# NEO-Pi-RAK-3.net
KiCad netlist of a schematic drawn in EAGLE
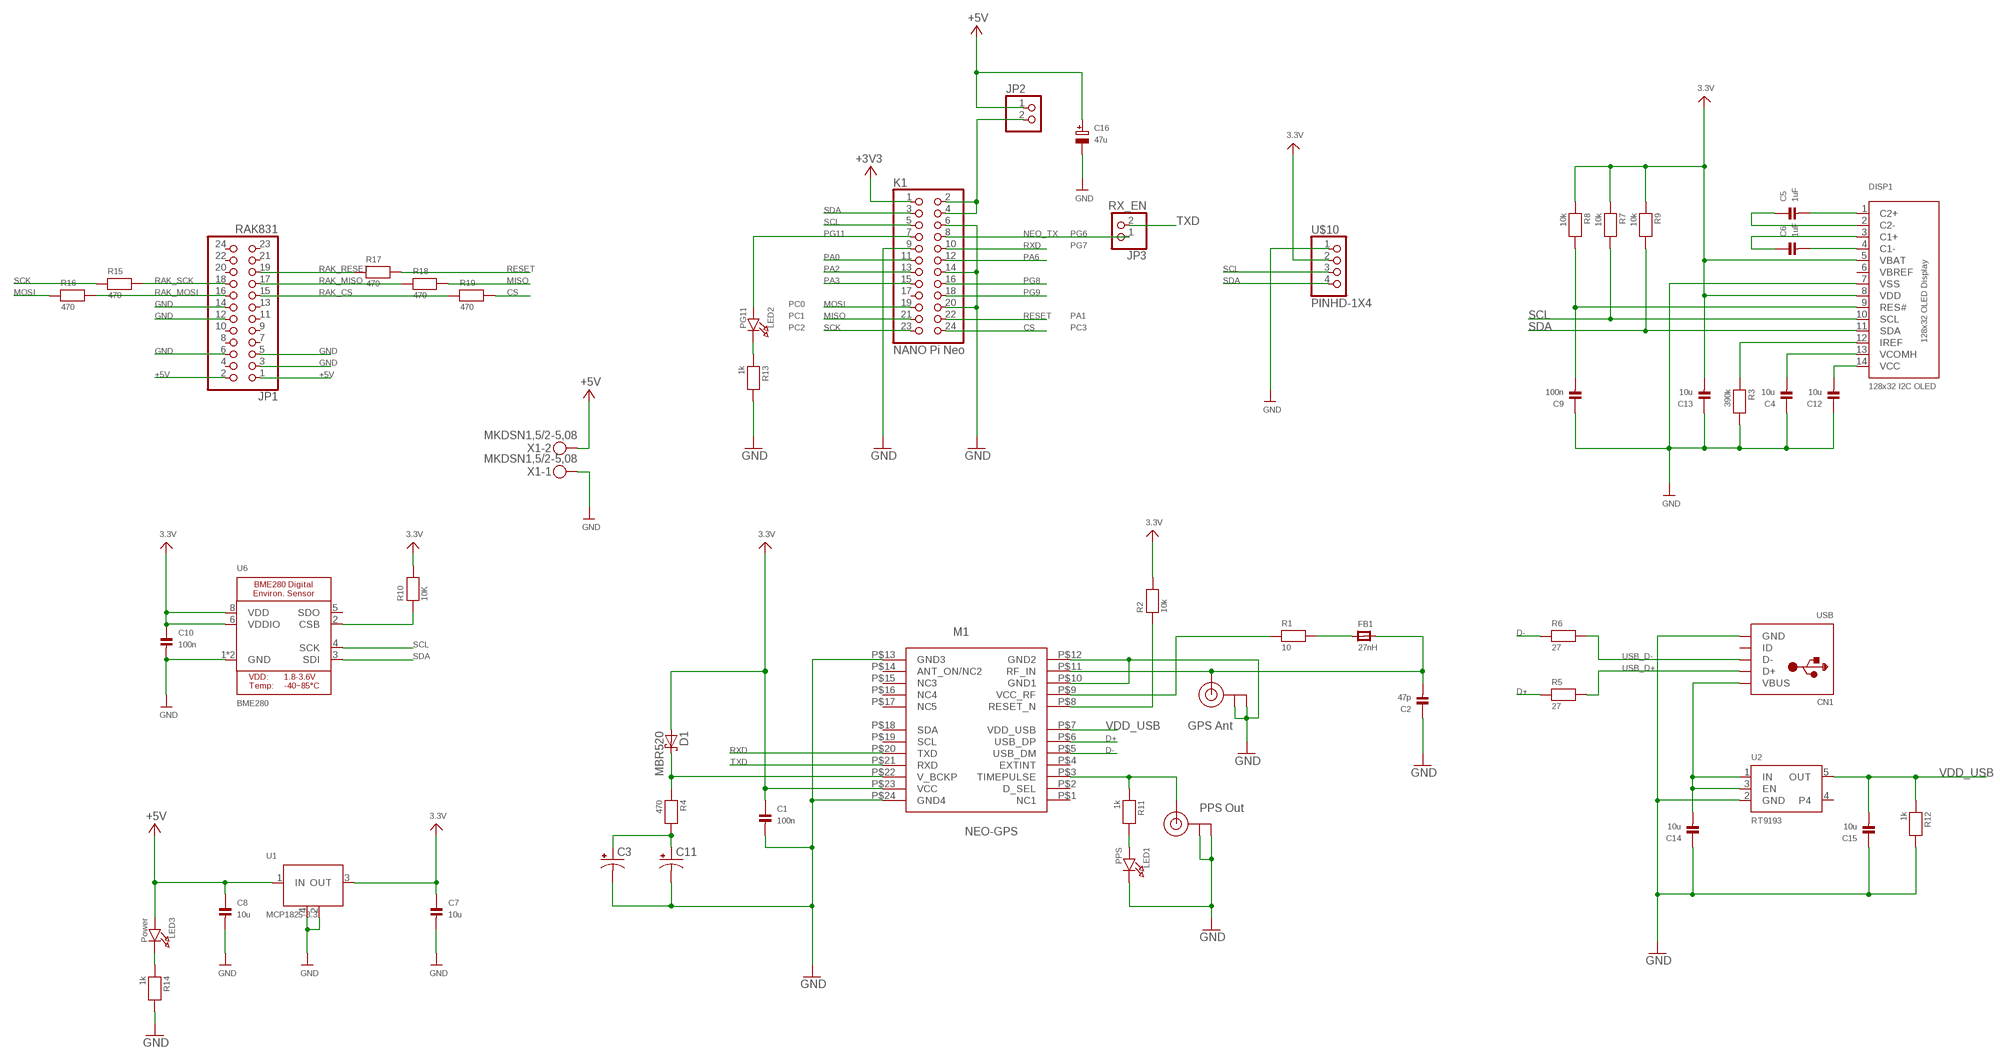
[diagram p0: schematic, sheet 1]

(export (version "E")
  (design (tool "Eeschema 10.0.6"))
  (components
    (comp (ref "C1")
      (value "100n")
      (footprint "eagle-import:0805")
      (libsource (lib "eagle-import") (part "CAP_CERAMIC0805"))
    )
    (comp (ref "C2")
      (value "47p")
      (footprint "eagle-import:0805")
      (libsource (lib "eagle-import") (part "CAP_CERAMIC0805"))
    )
    (comp (ref "C3")
      (value "SUPERCAP")
      (footprint "eagle-import:414-VA5R")
      (libsource (lib "eagle-import") (part "adafruit_SUPERCAP"))
    )
    (comp (ref "C4")
      (value "10u")
      (footprint "eagle-import:0805")
      (libsource (lib "eagle-import") (part "CAP_CERAMIC0805"))
    )
    (comp (ref "C5")
      (value "1uF")
      (footprint "eagle-import:0805")
      (libsource (lib "eagle-import") (part "CAP_CERAMIC0805"))
    )
    (comp (ref "C6")
      (value "1uF")
      (footprint "eagle-import:0805")
      (libsource (lib "eagle-import") (part "CAP_CERAMIC0805"))
    )
    (comp (ref "C7")
      (value "10u")
      (footprint "eagle-import:0805")
      (libsource (lib "eagle-import") (part "CAP_CERAMIC0805"))
    )
    (comp (ref "C8")
      (value "10u")
      (footprint "eagle-import:0805")
      (libsource (lib "eagle-import") (part "CAP_CERAMIC0805"))
    )
    (comp (ref "C9")
      (value "100n")
      (footprint "eagle-import:0805")
      (libsource (lib "eagle-import") (part "CAP_CERAMIC0805"))
    )
    (comp (ref "C10")
      (value "100n")
      (footprint "eagle-import:0805")
      (libsource (lib "eagle-import") (part "CAP_CERAMIC0805"))
    )
    (comp (ref "C11")
      (value "SUPERCAP")
      (footprint "eagle-import:SUPERCAP")
      (libsource (lib "eagle-import") (part "SUPERCAP"))
    )
    (comp (ref "C12")
      (value "10u")
      (footprint "eagle-import:0805")
      (libsource (lib "eagle-import") (part "CAP_CERAMIC0805"))
    )
    (comp (ref "C13")
      (value "10u")
      (footprint "eagle-import:0805")
      (libsource (lib "eagle-import") (part "CAP_CERAMIC0805"))
    )
    (comp (ref "C14")
      (value "10u")
      (footprint "eagle-import:0805")
      (libsource (lib "eagle-import") (part "CAP_CERAMIC0805"))
    )
    (comp (ref "C15")
      (value "10u")
      (footprint "eagle-import:0805")
      (libsource (lib "eagle-import") (part "CAP_CERAMIC0805"))
    )
    (comp (ref "C16")
      (value "47u")
      (footprint "eagle-import:EIA3528-21_B-R")
      (libsource (lib "eagle-import") (part "CAP_TANTALUMB/3528_REFLOW"))
    )
    (comp (ref "CN1")
      (value "USB")
      (footprint "eagle-import:USB-MINIB")
      (libsource (lib "eagle-import") (part "USBMINIB"))
    )
    (comp (ref "D1")
      (value "MBR520")
      (footprint "eagle-import:SOD123")
      (libsource (lib "eagle-import") (part "MBR0520"))
    )
    (comp (ref "DISP1")
      (value "128x32 I2C OLED")
      (footprint "eagle-import:0.91-128X32-OLED-I2C")
      (libsource (lib "eagle-import") (part "0.91-128X32-OLED-I2C"))
    )
    (comp (ref "FB1")
      (value "27nH")
      (footprint "eagle-import:0805")
      (libsource (lib "eagle-import") (part "FERRITE0805"))
    )
    (comp (ref "JP1")
      (value "RAK831")
      (footprint "eagle-import:2X12")
      (libsource (lib "eagle-import") (part "PINHD-2X12"))
    )
    (comp (ref "JP2")
      (value "PINHD-1X2")
      (footprint "eagle-import:1X02")
      (libsource (lib "eagle-import") (part "PINHD-1X2"))
    )
    (comp (ref "JP3")
      (value "RX_EN")
      (footprint "eagle-import:1X02")
      (libsource (lib "eagle-import") (part "PINHD-1X2"))
    )
    (comp (ref "K1")
      (value "NANO Pi Neo")
      (footprint "eagle-import:2X12")
      (libsource (lib "eagle-import") (part "PINHD-2X12"))
    )
    (comp (ref "LED1")
      (value "PPS")
      (footprint "eagle-import:CHIPLED_0805")
      (libsource (lib "eagle-import") (part "LED0805"))
    )
    (comp (ref "LED2")
      (value "PG11")
      (footprint "eagle-import:CHIPLED_0805")
      (libsource (lib "eagle-import") (part "LED0805"))
    )
    (comp (ref "LED3")
      (value "Power")
      (footprint "eagle-import:CHIPLED_0805")
      (libsource (lib "eagle-import") (part "LED0805"))
    )
    (comp (ref "M1")
      (value "NEO-GPS")
      (footprint "eagle-import:NEO_GPS")
      (libsource (lib "eagle-import") (part "NEO-GPS"))
    )
    (comp (ref "R1")
      (value "10")
      (footprint "eagle-import:0805")
      (libsource (lib "eagle-import") (part "RESISTOR0805"))
    )
    (comp (ref "R2")
      (value "10k")
      (footprint "eagle-import:0805")
      (libsource (lib "eagle-import") (part "RESISTOR0805"))
    )
    (comp (ref "R3")
      (value "390k")
      (footprint "eagle-import:0805")
      (libsource (lib "eagle-import") (part "RESISTOR0805"))
    )
    (comp (ref "R4")
      (value "470")
      (footprint "eagle-import:0805")
      (libsource (lib "eagle-import") (part "RESISTOR0805"))
    )
    (comp (ref "R5")
      (value "27")
      (footprint "eagle-import:0805")
      (libsource (lib "eagle-import") (part "RESISTOR0805"))
    )
    (comp (ref "R6")
      (value "27")
      (footprint "eagle-import:0805")
      (libsource (lib "eagle-import") (part "RESISTOR0805"))
    )
    (comp (ref "R7")
      (value "10k")
      (footprint "eagle-import:0805")
      (libsource (lib "eagle-import") (part "RESISTOR0805"))
    )
    (comp (ref "R8")
      (value "10k")
      (footprint "eagle-import:0805")
      (libsource (lib "eagle-import") (part "RESISTOR0805"))
    )
    (comp (ref "R9")
      (value "10k")
      (footprint "eagle-import:0805")
      (libsource (lib "eagle-import") (part "RESISTOR0805"))
    )
    (comp (ref "R10")
      (value "10K")
      (footprint "eagle-import:0805")
      (libsource (lib "eagle-import") (part "RESISTOR0805"))
    )
    (comp (ref "R11")
      (value "1k")
      (footprint "eagle-import:0805")
      (libsource (lib "eagle-import") (part "RESISTOR0805"))
    )
    (comp (ref "R12")
      (value "1k")
      (footprint "eagle-import:0805")
      (libsource (lib "eagle-import") (part "RESISTOR0805"))
    )
    (comp (ref "R13")
      (value "1k")
      (footprint "eagle-import:0805")
      (libsource (lib "eagle-import") (part "RESISTOR0805"))
    )
    (comp (ref "R14")
      (value "1k")
      (footprint "eagle-import:0805")
      (libsource (lib "eagle-import") (part "RESISTOR0805"))
    )
    (comp (ref "R15")
      (value "470")
      (footprint "eagle-import:0805")
      (libsource (lib "eagle-import") (part "RESISTOR0805"))
    )
    (comp (ref "R16")
      (value "470")
      (footprint "eagle-import:0805")
      (libsource (lib "eagle-import") (part "RESISTOR0805"))
    )
    (comp (ref "R17")
      (value "470")
      (footprint "eagle-import:0805")
      (libsource (lib "eagle-import") (part "RESISTOR0805"))
    )
    (comp (ref "R18")
      (value "470")
      (footprint "eagle-import:0805")
      (libsource (lib "eagle-import") (part "RESISTOR0805"))
    )
    (comp (ref "R19")
      (value "470")
      (footprint "eagle-import:0805")
      (libsource (lib "eagle-import") (part "RESISTOR0805"))
    )
    (comp (ref "U$1")
      (value "U.FL")
      (footprint "eagle-import:U.FL")
      (libsource (lib "eagle-import") (part "U.FL"))
    )
    (comp (ref "U$2")
      (value "U.FL")
      (footprint "eagle-import:U.FL")
      (libsource (lib "eagle-import") (part "U.FL"))
    )
    (comp (ref "U$10")
      (value "PINHD-1X4")
      (footprint "eagle-import:1X04-BIG")
      (libsource (lib "eagle-import") (part "PINHD-1X4"))
    )
    (comp (ref "U1")
      (value "MCP1825-3.3")
      (footprint "eagle-import:UA78M05")
      (libsource (lib "eagle-import") (part "MCP1825ST-3.3"))
    )
    (comp (ref "U2")
      (value "RT9193")
      (footprint "eagle-import:SOT23-5")
      (libsource (lib "eagle-import") (part "VREG_SOT23-5"))
    )
    (comp (ref "U6")
      (value "BME280")
      (footprint "eagle-import:BME280")
      (libsource (lib "eagle-import") (part "BME280"))
    )
    (comp (ref "X1")
      (value "MKDSN1,5/2-5,08")
      (footprint "eagle-import:MKDSN1,5_2-5,08")
      (libsource (lib "eagle-import") (part "MKDSN1,5/2-5,08"))
    )
  )
  (nets
    (net (code "1") (name "+3V3") (class "Default")
      (node (ref "K1") (pin "1") (pinfunction "1_1") (pintype "passive"))
    )
    (net (code "2") (name "+5V") (class "Default")
      (node (ref "C16") (pin "+") (pinfunction "+_+") (pintype "passive"))
      (node (ref "C8") (pin "1") (pinfunction "P$1_1") (pintype "passive"))
      (node (ref "JP1") (pin "1") (pinfunction "1_1") (pintype "passive"))
      (node (ref "JP1") (pin "2") (pinfunction "2_2") (pintype "passive"))
      (node (ref "JP2") (pin "1") (pinfunction "1_1") (pintype "passive"))
      (node (ref "LED3") (pin "A") (pinfunction "A_A") (pintype "passive"))
      (node (ref "U1") (pin "1") (pinfunction "IN_1") (pintype "input"))
      (node (ref "X1") (pin "2") (pinfunction "KL_2") (pintype "passive"))
    )
    (net (code "3") (name "/CS") (class "Default")
      (node (ref "K1") (pin "24") (pinfunction "24_24") (pintype "passive"))
      (node (ref "R19") (pin "2") (pinfunction "2_2") (pintype "passive"))
    )
    (net (code "4") (name "/D+") (class "Default")
      (node (ref "M1") (pin "P$6") (pinfunction "USB_DP_P$6") (pintype "bidirectional"))
      (node (ref "R5") (pin "1") (pinfunction "1_1") (pintype "passive"))
    )
    (net (code "5") (name "/D-") (class "Default")
      (node (ref "M1") (pin "P$5") (pinfunction "USB_DM_P$5") (pintype "bidirectional"))
      (node (ref "R6") (pin "1") (pinfunction "1_1") (pintype "passive"))
    )
    (net (code "6") (name "/MISO") (class "Default")
      (node (ref "K1") (pin "21") (pinfunction "21_21") (pintype "passive"))
      (node (ref "R18") (pin "2") (pinfunction "2_2") (pintype "passive"))
    )
    (net (code "7") (name "/MOSI") (class "Default")
      (node (ref "K1") (pin "19") (pinfunction "19_19") (pintype "passive"))
      (node (ref "R16") (pin "1") (pinfunction "1_1") (pintype "passive"))
    )
    (net (code "8") (name "/NEO_TX") (class "Default")
      (node (ref "JP3") (pin "1") (pinfunction "1_1") (pintype "passive"))
      (node (ref "K1") (pin "8") (pinfunction "8_8") (pintype "passive"))
    )
    (net (code "9") (name "/PA0") (class "Default")
      (node (ref "K1") (pin "11") (pinfunction "11_11") (pintype "passive"))
    )
    (net (code "10") (name "/PA2") (class "Default")
      (node (ref "K1") (pin "13") (pinfunction "13_13") (pintype "passive"))
    )
    (net (code "11") (name "/PA3") (class "Default")
      (node (ref "K1") (pin "15") (pinfunction "15_15") (pintype "passive"))
    )
    (net (code "12") (name "/PA6") (class "Default")
      (node (ref "K1") (pin "12") (pinfunction "12_12") (pintype "passive"))
    )
    (net (code "13") (name "/PG8") (class "Default")
      (node (ref "K1") (pin "16") (pinfunction "16_16") (pintype "passive"))
    )
    (net (code "14") (name "/PG9") (class "Default")
      (node (ref "K1") (pin "18") (pinfunction "18_18") (pintype "passive"))
    )
    (net (code "15") (name "/PG11") (class "Default")
      (node (ref "K1") (pin "7") (pinfunction "7_7") (pintype "passive"))
      (node (ref "LED2") (pin "A") (pinfunction "A_A") (pintype "passive"))
    )
    (net (code "16") (name "/RAK_CS") (class "Default")
      (node (ref "JP1") (pin "15") (pinfunction "15_15") (pintype "passive"))
      (node (ref "R19") (pin "1") (pinfunction "1_1") (pintype "passive"))
    )
    (net (code "17") (name "/RAK_MISO") (class "Default")
      (node (ref "JP1") (pin "17") (pinfunction "17_17") (pintype "passive"))
      (node (ref "R18") (pin "1") (pinfunction "1_1") (pintype "passive"))
    )
    (net (code "18") (name "/RAK_MOSI") (class "Default")
      (node (ref "JP1") (pin "16") (pinfunction "16_16") (pintype "passive"))
      (node (ref "R16") (pin "2") (pinfunction "2_2") (pintype "passive"))
    )
    (net (code "19") (name "/RAK_RESET") (class "Default")
      (node (ref "JP1") (pin "19") (pinfunction "19_19") (pintype "passive"))
      (node (ref "R17") (pin "1") (pinfunction "1_1") (pintype "passive"))
    )
    (net (code "20") (name "/RAK_SCK") (class "Default")
      (node (ref "JP1") (pin "18") (pinfunction "18_18") (pintype "passive"))
      (node (ref "R15") (pin "2") (pinfunction "2_2") (pintype "passive"))
    )
    (net (code "21") (name "/RESET") (class "Default")
      (node (ref "K1") (pin "22") (pinfunction "22_22") (pintype "passive"))
      (node (ref "R17") (pin "2") (pinfunction "2_2") (pintype "passive"))
    )
    (net (code "22") (name "/RXD") (class "Default")
      (node (ref "K1") (pin "10") (pinfunction "10_10") (pintype "passive"))
      (node (ref "M1") (pin "P$20") (pinfunction "TXD_P$20") (pintype "output"))
    )
    (net (code "23") (name "/SCK") (class "Default")
      (node (ref "K1") (pin "23") (pinfunction "23_23") (pintype "passive"))
      (node (ref "R15") (pin "1") (pinfunction "1_1") (pintype "passive"))
    )
    (net (code "24") (name "/SCL") (class "Default")
      (node (ref "DISP1") (pin "10") (pinfunction "SCL_10") (pintype "bidirectional"))
      (node (ref "K1") (pin "5") (pinfunction "5_5") (pintype "passive"))
      (node (ref "R7") (pin "2") (pinfunction "2_2") (pintype "passive"))
      (node (ref "U$10") (pin "3") (pinfunction "3_3") (pintype "passive"))
      (node (ref "U6") (pin "4") (pinfunction "SCK_4") (pintype "input"))
    )
    (net (code "25") (name "/SDA") (class "Default")
      (node (ref "DISP1") (pin "11") (pinfunction "SDA_11") (pintype "bidirectional"))
      (node (ref "K1") (pin "3") (pinfunction "3_3") (pintype "passive"))
      (node (ref "R9") (pin "2") (pinfunction "2_2") (pintype "passive"))
      (node (ref "U$10") (pin "4") (pinfunction "4_4") (pintype "passive"))
      (node (ref "U6") (pin "3") (pinfunction "SDI_3") (pintype "input"))
    )
    (net (code "26") (name "/TXD") (class "Default")
      (node (ref "JP3") (pin "2") (pinfunction "2_2") (pintype "passive"))
      (node (ref "M1") (pin "P$21") (pinfunction "RXD_P$21") (pintype "input"))
    )
    (net (code "27") (name "/USB_D+") (class "Default")
      (node (ref "CN1") (pin "D+") (pinfunction "D+_D+") (pintype "bidirectional"))
      (node (ref "R5") (pin "2") (pinfunction "2_2") (pintype "passive"))
    )
    (net (code "28") (name "/USB_D-") (class "Default")
      (node (ref "CN1") (pin "D-") (pinfunction "D-_D-") (pintype "bidirectional"))
      (node (ref "R6") (pin "2") (pinfunction "2_2") (pintype "passive"))
    )
    (net (code "29") (name "/VBREF") (class "Default")
      (node (ref "DISP1") (pin "6") (pinfunction "VBREF_6") (pintype "power_in"))
    )
    (net (code "30") (name "/VDD_USB") (class "Default")
      (node (ref "C15") (pin "2") (pinfunction "P$2_2") (pintype "passive"))
      (node (ref "M1") (pin "P$7") (pinfunction "VDD_USB_P$7") (pintype "input"))
      (node (ref "R12") (pin "1") (pinfunction "1_1") (pintype "passive"))
      (node (ref "U2") (pin "5") (pinfunction "OUT_5") (pintype "bidirectional"))
    )
    (net (code "31") (name "3.3V") (class "Default")
      (node (ref "C1") (pin "1") (pinfunction "P$1_1") (pintype "passive"))
      (node (ref "C10") (pin "1") (pinfunction "P$1_1") (pintype "passive"))
      (node (ref "C13") (pin "2") (pinfunction "P$2_2") (pintype "passive"))
      (node (ref "C7") (pin "1") (pinfunction "P$1_1") (pintype "passive"))
      (node (ref "D1") (pin "A") (pinfunction "A_A") (pintype "passive"))
      (node (ref "DISP1") (pin "5") (pinfunction "VBAT_5") (pintype "power_in"))
      (node (ref "DISP1") (pin "8") (pinfunction "VDD_8") (pintype "power_in"))
      (node (ref "M1") (pin "P$23") (pinfunction "VCC_P$23") (pintype "input"))
      (node (ref "R10") (pin "2") (pinfunction "2_2") (pintype "passive"))
      (node (ref "R2") (pin "2") (pinfunction "2_2") (pintype "passive"))
      (node (ref "R7") (pin "1") (pinfunction "1_1") (pintype "passive"))
      (node (ref "R8") (pin "1") (pinfunction "1_1") (pintype "passive"))
      (node (ref "R9") (pin "1") (pinfunction "1_1") (pintype "passive"))
      (node (ref "U$10") (pin "2") (pinfunction "2_2") (pintype "passive"))
      (node (ref "U1") (pin "3") (pinfunction "OUT_3") (pintype "passive"))
      (node (ref "U6") (pin "6") (pinfunction "VDDIO_6") (pintype "power_in"))
      (node (ref "U6") (pin "8") (pinfunction "VDD_8") (pintype "power_in"))
    )
    (net (code "32") (name "GND") (class "Default")
      (node (ref "C1") (pin "2") (pinfunction "P$2_2") (pintype "passive"))
      (node (ref "C10") (pin "2") (pinfunction "P$2_2") (pintype "passive"))
      (node (ref "C11") (pin "P$2") (pinfunction "-_P$2") (pintype "passive"))
      (node (ref "C12") (pin "1") (pinfunction "P$1_1") (pintype "passive"))
      (node (ref "C13") (pin "1") (pinfunction "P$1_1") (pintype "passive"))
      (node (ref "C14") (pin "1") (pinfunction "P$1_1") (pintype "passive"))
      (node (ref "C15") (pin "1") (pinfunction "P$1_1") (pintype "passive"))
      (node (ref "C16") (pin "-") (pinfunction "-_-") (pintype "passive"))
      (node (ref "C2") (pin "1") (pinfunction "P$1_1") (pintype "passive"))
      (node (ref "C3") (pin "-") (pinfunction "-_-") (pintype "passive"))
      (node (ref "C4") (pin "1") (pinfunction "P$1_1") (pintype "passive"))
      (node (ref "C7") (pin "2") (pinfunction "P$2_2") (pintype "passive"))
      (node (ref "C8") (pin "2") (pinfunction "P$2_2") (pintype "passive"))
      (node (ref "C9") (pin "1") (pinfunction "P$1_1") (pintype "passive"))
      (node (ref "CN1") (pin "GND") (pinfunction "GND_GND") (pintype "power_in"))
      (node (ref "DISP1") (pin "7") (pinfunction "VSS_7") (pintype "power_in"))
      (node (ref "JP1") (pin "12") (pinfunction "12_12") (pintype "passive"))
      (node (ref "JP1") (pin "14") (pinfunction "14_14") (pintype "passive"))
      (node (ref "JP1") (pin "3") (pinfunction "3_3") (pintype "passive"))
      (node (ref "JP1") (pin "5") (pinfunction "5_5") (pintype "passive"))
      (node (ref "JP1") (pin "6") (pinfunction "6_6") (pintype "passive"))
      (node (ref "K1") (pin "14") (pinfunction "14_14") (pintype "passive"))
      (node (ref "K1") (pin "20") (pinfunction "20_20") (pintype "passive"))
      (node (ref "K1") (pin "6") (pinfunction "6_6") (pintype "passive"))
      (node (ref "K1") (pin "9") (pinfunction "9_9") (pintype "passive"))
      (node (ref "LED1") (pin "C") (pinfunction "C_C") (pintype "passive"))
      (node (ref "M1") (pin "P$10") (pinfunction "GND1_P$10") (pintype "input"))
      (node (ref "M1") (pin "P$12") (pinfunction "GND2_P$12") (pintype "input"))
      (node (ref "M1") (pin "P$13") (pinfunction "GND3_P$13") (pintype "input"))
      (node (ref "M1") (pin "P$24") (pinfunction "GND4_P$24") (pintype "input"))
      (node (ref "R12") (pin "2") (pinfunction "2_2") (pintype "passive"))
      (node (ref "R13") (pin "2") (pinfunction "2_2") (pintype "passive"))
      (node (ref "R14") (pin "2") (pinfunction "2_2") (pintype "passive"))
      (node (ref "R3") (pin "2") (pinfunction "2_2") (pintype "passive"))
      (node (ref "U$1") (pin "P$1") (pinfunction "GND_P$1") (pintype "bidirectional"))
      (node (ref "U$1") (pin "P$2") (pinfunction "GND_P$2") (pintype "bidirectional"))
      (node (ref "U$10") (pin "1") (pinfunction "1_1") (pintype "passive"))
      (node (ref "U$2") (pin "P$1") (pinfunction "GND_P$1") (pintype "bidirectional"))
      (node (ref "U$2") (pin "P$2") (pinfunction "GND_P$2") (pintype "bidirectional"))
      (node (ref "U1") (pin "2") (pinfunction "COMMON1_2") (pintype "passive"))
      (node (ref "U1") (pin "4") (pinfunction "COMMON2_4") (pintype "passive"))
      (node (ref "U2") (pin "2") (pinfunction "GND_2") (pintype "bidirectional"))
      (node (ref "U6") (pin "1") (pinfunction "GND_1") (pintype "power_in"))
      (node (ref "U6") (pin "7") (pinfunction "GND_7") (pintype "power_in"))
      (node (ref "X1") (pin "1") (pinfunction "KL_1") (pintype "passive"))
    )
    (net (code "33") (name "Net-(C2-P$2)") (class "Default")
      (node (ref "C2") (pin "2") (pinfunction "P$2_2") (pintype "passive"))
      (node (ref "FB1") (pin "2") (pinfunction "P$2_2") (pintype "passive"))
      (node (ref "M1") (pin "P$11") (pinfunction "RF_IN_P$11") (pintype "input"))
      (node (ref "U$1") (pin "P$3") (pinfunction "SIGNAL_P$3") (pintype "bidirectional"))
    )
    (net (code "34") (name "Net-(C4-P$2)") (class "Default")
      (node (ref "C4") (pin "2") (pinfunction "P$2_2") (pintype "passive"))
      (node (ref "DISP1") (pin "13") (pinfunction "VCOMH_13") (pintype "power_in"))
    )
    (net (code "35") (name "Net-(C5-P$1)") (class "Default")
      (node (ref "C5") (pin "1") (pinfunction "P$1_1") (pintype "passive"))
      (node (ref "DISP1") (pin "2") (pinfunction "C2-_2") (pintype "bidirectional"))
    )
    (net (code "36") (name "Net-(C5-P$2)") (class "Default")
      (node (ref "C5") (pin "2") (pinfunction "P$2_2") (pintype "passive"))
      (node (ref "DISP1") (pin "1") (pinfunction "C2+_1") (pintype "bidirectional"))
    )
    (net (code "37") (name "Net-(C6-P$1)") (class "Default")
      (node (ref "C6") (pin "1") (pinfunction "P$1_1") (pintype "passive"))
      (node (ref "DISP1") (pin "3") (pinfunction "C1+_3") (pintype "bidirectional"))
    )
    (net (code "38") (name "Net-(C6-P$2)") (class "Default")
      (node (ref "C6") (pin "2") (pinfunction "P$2_2") (pintype "passive"))
      (node (ref "DISP1") (pin "4") (pinfunction "C1-_4") (pintype "bidirectional"))
    )
    (net (code "39") (name "Net-(C9-P$2)") (class "Default")
      (node (ref "C9") (pin "2") (pinfunction "P$2_2") (pintype "passive"))
      (node (ref "DISP1") (pin "9") (pinfunction "RES#_9") (pintype "bidirectional"))
      (node (ref "R8") (pin "2") (pinfunction "2_2") (pintype "passive"))
    )
    (net (code "40") (name "Net-(C11-+)") (class "Default")
      (node (ref "C11") (pin "P$1") (pinfunction "+_P$1") (pintype "passive"))
      (node (ref "C3") (pin "+") (pinfunction "+_+") (pintype "passive"))
      (node (ref "R4") (pin "2") (pinfunction "2_2") (pintype "passive"))
    )
    (net (code "41") (name "Net-(C12-P$2)") (class "Default")
      (node (ref "C12") (pin "2") (pinfunction "P$2_2") (pintype "passive"))
      (node (ref "DISP1") (pin "14") (pinfunction "VCC_14") (pintype "power_in"))
    )
    (net (code "42") (name "Net-(C14-P$2)") (class "Default")
      (node (ref "C14") (pin "2") (pinfunction "P$2_2") (pintype "passive"))
      (node (ref "CN1") (pin "VBUS") (pinfunction "VBUS_VBUS") (pintype "power_in"))
      (node (ref "U2") (pin "1") (pinfunction "IN_1") (pintype "bidirectional"))
      (node (ref "U2") (pin "3") (pinfunction "EN_3") (pintype "bidirectional"))
    )
    (net (code "43") (name "Net-(DISP1-IREF)") (class "Default")
      (node (ref "DISP1") (pin "12") (pinfunction "IREF_12") (pintype "bidirectional"))
      (node (ref "R3") (pin "1") (pinfunction "1_1") (pintype "passive"))
    )
    (net (code "44") (name "Net-(FB1-P$1)") (class "Default")
      (node (ref "FB1") (pin "1") (pinfunction "P$1_1") (pintype "passive"))
      (node (ref "R1") (pin "2") (pinfunction "2_2") (pintype "passive"))
    )
    (net (code "45") (name "Net-(JP2-Pad2)") (class "Default")
      (node (ref "JP2") (pin "2") (pinfunction "2_2") (pintype "passive"))
      (node (ref "K1") (pin "2") (pinfunction "2_2") (pintype "passive"))
      (node (ref "K1") (pin "4") (pinfunction "4_4") (pintype "passive"))
    )
    (net (code "46") (name "Net-(LED1-PadA)") (class "Default")
      (node (ref "LED1") (pin "A") (pinfunction "A_A") (pintype "passive"))
      (node (ref "R11") (pin "2") (pinfunction "2_2") (pintype "passive"))
    )
    (net (code "47") (name "Net-(LED2-PadC)") (class "Default")
      (node (ref "LED2") (pin "C") (pinfunction "C_C") (pintype "passive"))
      (node (ref "R13") (pin "1") (pinfunction "1_1") (pintype "passive"))
    )
    (net (code "48") (name "Net-(LED3-PadC)") (class "Default")
      (node (ref "LED3") (pin "C") (pinfunction "C_C") (pintype "passive"))
      (node (ref "R14") (pin "1") (pinfunction "1_1") (pintype "passive"))
    )
    (net (code "49") (name "Net-(M1-RESET_N)") (class "Default")
      (node (ref "M1") (pin "P$8") (pinfunction "RESET_N_P$8") (pintype "input"))
      (node (ref "R2") (pin "1") (pinfunction "1_1") (pintype "passive"))
    )
    (net (code "50") (name "Net-(M1-TIMEPULSE)") (class "Default")
      (node (ref "M1") (pin "P$3") (pinfunction "TIMEPULSE_P$3") (pintype "output"))
      (node (ref "R11") (pin "1") (pinfunction "1_1") (pintype "passive"))
      (node (ref "U$2") (pin "P$3") (pinfunction "SIGNAL_P$3") (pintype "bidirectional"))
    )
    (net (code "51") (name "Net-(M1-VCC_RF)") (class "Default")
      (node (ref "M1") (pin "P$9") (pinfunction "VCC_RF_P$9") (pintype "output"))
      (node (ref "R1") (pin "1") (pinfunction "1_1") (pintype "passive"))
    )
    (net (code "52") (name "Net-(M1-V_BCKP)") (class "Default")
      (node (ref "D1") (pin "C") (pinfunction "C_C") (pintype "passive"))
      (node (ref "M1") (pin "P$22") (pinfunction "V_BCKP_P$22") (pintype "input"))
      (node (ref "R4") (pin "1") (pinfunction "1_1") (pintype "passive"))
    )
    (net (code "53") (name "Net-(U6-CSB)") (class "Default")
      (node (ref "R10") (pin "1") (pinfunction "1_1") (pintype "passive"))
      (node (ref "U6") (pin "2") (pinfunction "CSB_2") (pintype "input"))
    )
    (net (code "54") (name "unconnected-(CN1-PadID)") (class "Default")
      (node (ref "CN1") (pin "ID") (pinfunction "ID_ID") (pintype "bidirectional"))
    )
    (net (code "55") (name "unconnected-(JP1-Pad4)") (class "Default")
      (node (ref "JP1") (pin "4") (pinfunction "4_4") (pintype "passive"))
    )
    (net (code "56") (name "unconnected-(JP1-Pad7)") (class "Default")
      (node (ref "JP1") (pin "7") (pinfunction "7_7") (pintype "passive"))
    )
    (net (code "57") (name "unconnected-(JP1-Pad8)") (class "Default")
      (node (ref "JP1") (pin "8") (pinfunction "8_8") (pintype "passive"))
    )
    (net (code "58") (name "unconnected-(JP1-Pad9)") (class "Default")
      (node (ref "JP1") (pin "9") (pinfunction "9_9") (pintype "passive"))
    )
    (net (code "59") (name "unconnected-(JP1-Pad10)") (class "Default")
      (node (ref "JP1") (pin "10") (pinfunction "10_10") (pintype "passive"))
    )
    (net (code "60") (name "unconnected-(JP1-Pad11)") (class "Default")
      (node (ref "JP1") (pin "11") (pinfunction "11_11") (pintype "passive"))
    )
    (net (code "61") (name "unconnected-(JP1-Pad13)") (class "Default")
      (node (ref "JP1") (pin "13") (pinfunction "13_13") (pintype "passive"))
    )
    (net (code "62") (name "unconnected-(JP1-Pad20)") (class "Default")
      (node (ref "JP1") (pin "20") (pinfunction "20_20") (pintype "passive"))
    )
    (net (code "63") (name "unconnected-(JP1-Pad21)") (class "Default")
      (node (ref "JP1") (pin "21") (pinfunction "21_21") (pintype "passive"))
    )
    (net (code "64") (name "unconnected-(JP1-Pad22)") (class "Default")
      (node (ref "JP1") (pin "22") (pinfunction "22_22") (pintype "passive"))
    )
    (net (code "65") (name "unconnected-(JP1-Pad23)") (class "Default")
      (node (ref "JP1") (pin "23") (pinfunction "23_23") (pintype "passive"))
    )
    (net (code "66") (name "unconnected-(JP1-Pad24)") (class "Default")
      (node (ref "JP1") (pin "24") (pinfunction "24_24") (pintype "passive"))
    )
    (net (code "67") (name "unconnected-(K1-Pad17)") (class "Default")
      (node (ref "K1") (pin "17") (pinfunction "17_17") (pintype "passive"))
    )
    (net (code "68") (name "unconnected-(M1-ANT_ON{slash}NC2-PadP$14)") (class "Default")
      (node (ref "M1") (pin "P$14") (pinfunction "ANT_ON/NC2_P$14") (pintype "bidirectional"))
    )
    (net (code "69") (name "unconnected-(M1-D_SEL-PadP$2)") (class "Default")
      (node (ref "M1") (pin "P$2") (pinfunction "D_SEL_P$2") (pintype "input"))
    )
    (net (code "70") (name "unconnected-(M1-EXTINT-PadP$4)") (class "Default")
      (node (ref "M1") (pin "P$4") (pinfunction "EXTINT_P$4") (pintype "input"))
    )
    (net (code "71") (name "unconnected-(M1-NC1-PadP$1)") (class "Default")
      (node (ref "M1") (pin "P$1") (pinfunction "NC1_P$1") (pintype "no_connect"))
    )
    (net (code "72") (name "unconnected-(M1-NC3-PadP$15)") (class "Default")
      (node (ref "M1") (pin "P$15") (pinfunction "NC3_P$15") (pintype "no_connect"))
    )
    (net (code "73") (name "unconnected-(M1-NC4-PadP$16)") (class "Default")
      (node (ref "M1") (pin "P$16") (pinfunction "NC4_P$16") (pintype "no_connect"))
    )
    (net (code "74") (name "unconnected-(M1-NC5-PadP$17)") (class "Default")
      (node (ref "M1") (pin "P$17") (pinfunction "NC5_P$17") (pintype "no_connect"))
    )
    (net (code "75") (name "unconnected-(M1-SCL-PadP$19)") (class "Default")
      (node (ref "M1") (pin "P$19") (pinfunction "SCL_P$19") (pintype "bidirectional"))
    )
    (net (code "76") (name "unconnected-(M1-SDA-PadP$18)") (class "Default")
      (node (ref "M1") (pin "P$18") (pinfunction "SDA_P$18") (pintype "bidirectional"))
    )
    (net (code "77") (name "unconnected-(U2-P4-Pad4)") (class "Default")
      (node (ref "U2") (pin "4") (pinfunction "P4_4") (pintype "bidirectional"))
    )
    (net (code "78") (name "unconnected-(U6-SDO-Pad5)") (class "Default")
      (node (ref "U6") (pin "5") (pinfunction "SDO_5") (pintype "output"))
    )
  )
)
